# CW340_EdgeConnector.net
KiCad netlist of a schematic drawn in Altium Designer
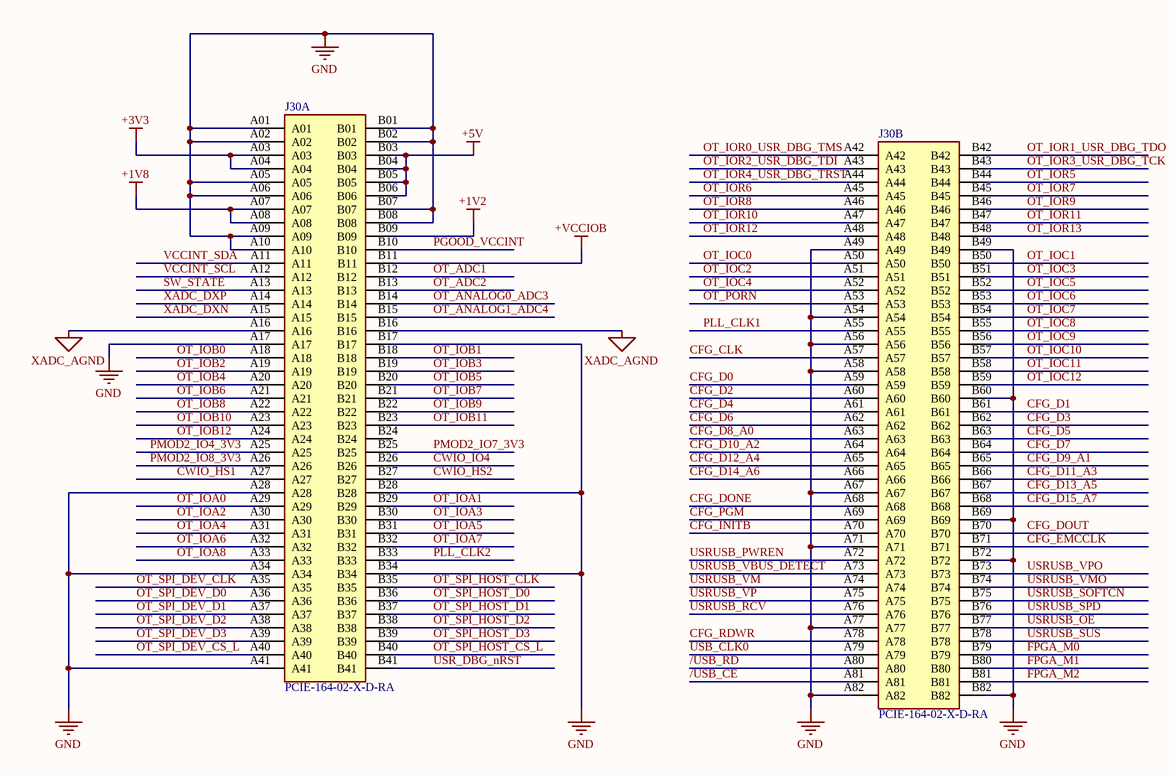
[diagram p0: CW340_EdgeConnector.SchDoc]

(export (version "E")
  (design (tool "Eeschema 10.0.6"))
  (components
    (comp (ref "J30")
      (value "PCIE-164-02-X-D-RA")
      (footprint "SAMTEC_PCIE-164-02-X-D-RA")
      (description "1.00 mm PCI ExpressÂ® Edge Card Connector")
      (fields (field (name "MF") "Samtec"))
      (libsource (lib "PCIE-164-02-X-D-RA") (part "PCIE-164-02-X-D-RA"))
    )
  )
  (nets
    (net (code "1") (name "+1V2") (class "Default")
      (node (ref "J30") (pin "B09") (pinfunction "B09_B09") (pintype "passive"))
    )
    (net (code "2") (name "+1V8") (class "Default")
      (node (ref "J30") (pin "A07") (pinfunction "A07_A07") (pintype "passive"))
      (node (ref "J30") (pin "A08") (pinfunction "A08_A08") (pintype "passive"))
    )
    (net (code "3") (name "+3V3") (class "Default")
      (node (ref "J30") (pin "A03") (pinfunction "A03_A03") (pintype "passive"))
      (node (ref "J30") (pin "A04") (pinfunction "A04_A04") (pintype "passive"))
    )
    (net (code "4") (name "+5V") (class "Default")
      (node (ref "J30") (pin "B03") (pinfunction "B03_B03") (pintype "passive"))
      (node (ref "J30") (pin "B04") (pinfunction "B04_B04") (pintype "passive"))
      (node (ref "J30") (pin "B05") (pinfunction "B05_B05") (pintype "passive"))
      (node (ref "J30") (pin "B06") (pinfunction "B06_B06") (pintype "passive"))
    )
    (net (code "5") (name "+VCCIOB") (class "Default")
      (node (ref "J30") (pin "B11") (pinfunction "B11_B11") (pintype "passive"))
    )
    (net (code "6") (name "/CFG_CLK") (class "Default")
      (node (ref "J30") (pin "A57") (pinfunction "A57_A57") (pintype "passive"))
    )
    (net (code "7") (name "/CFG_D0") (class "Default")
      (node (ref "J30") (pin "A59") (pinfunction "A59_A59") (pintype "passive"))
    )
    (net (code "8") (name "/CFG_D1") (class "Default")
      (node (ref "J30") (pin "B61") (pinfunction "B61_B61") (pintype "passive"))
    )
    (net (code "9") (name "/CFG_D2") (class "Default")
      (node (ref "J30") (pin "A60") (pinfunction "A60_A60") (pintype "passive"))
    )
    (net (code "10") (name "/CFG_D3") (class "Default")
      (node (ref "J30") (pin "B62") (pinfunction "B62_B62") (pintype "passive"))
    )
    (net (code "11") (name "/CFG_D4") (class "Default")
      (node (ref "J30") (pin "A61") (pinfunction "A61_A61") (pintype "passive"))
    )
    (net (code "12") (name "/CFG_D5") (class "Default")
      (node (ref "J30") (pin "B63") (pinfunction "B63_B63") (pintype "passive"))
    )
    (net (code "13") (name "/CFG_D6") (class "Default")
      (node (ref "J30") (pin "A62") (pinfunction "A62_A62") (pintype "passive"))
    )
    (net (code "14") (name "/CFG_D7") (class "Default")
      (node (ref "J30") (pin "B64") (pinfunction "B64_B64") (pintype "passive"))
    )
    (net (code "15") (name "/CFG_D8_A0") (class "Default")
      (node (ref "J30") (pin "A63") (pinfunction "A63_A63") (pintype "passive"))
    )
    (net (code "16") (name "/CFG_D9_A1") (class "Default")
      (node (ref "J30") (pin "B65") (pinfunction "B65_B65") (pintype "passive"))
    )
    (net (code "17") (name "/CFG_D10_A2") (class "Default")
      (node (ref "J30") (pin "A64") (pinfunction "A64_A64") (pintype "passive"))
    )
    (net (code "18") (name "/CFG_D11_A3") (class "Default")
      (node (ref "J30") (pin "B66") (pinfunction "B66_B66") (pintype "passive"))
    )
    (net (code "19") (name "/CFG_D12_A4") (class "Default")
      (node (ref "J30") (pin "A65") (pinfunction "A65_A65") (pintype "passive"))
    )
    (net (code "20") (name "/CFG_D13_A5") (class "Default")
      (node (ref "J30") (pin "B67") (pinfunction "B67_B67") (pintype "passive"))
    )
    (net (code "21") (name "/CFG_D14_A6") (class "Default")
      (node (ref "J30") (pin "A66") (pinfunction "A66_A66") (pintype "passive"))
    )
    (net (code "22") (name "/CFG_D15_A7") (class "Default")
      (node (ref "J30") (pin "B68") (pinfunction "B68_B68") (pintype "passive"))
    )
    (net (code "23") (name "/CFG_DONE") (class "Default")
      (node (ref "J30") (pin "A68") (pinfunction "A68_A68") (pintype "passive"))
    )
    (net (code "24") (name "/CFG_DOUT") (class "Default")
      (node (ref "J30") (pin "B70") (pinfunction "B70_B70") (pintype "passive"))
    )
    (net (code "25") (name "/CFG_EMCCLK") (class "Default")
      (node (ref "J30") (pin "B71") (pinfunction "B71_B71") (pintype "passive"))
    )
    (net (code "26") (name "/CFG_INITB") (class "Default")
      (node (ref "J30") (pin "A70") (pinfunction "A70_A70") (pintype "passive"))
    )
    (net (code "27") (name "/CFG_PGM") (class "Default")
      (node (ref "J30") (pin "A69") (pinfunction "A69_A69") (pintype "passive"))
    )
    (net (code "28") (name "/CFG_RDWR") (class "Default")
      (node (ref "J30") (pin "A78") (pinfunction "A78_A78") (pintype "passive"))
    )
    (net (code "29") (name "/CWIO_HS1") (class "Default")
      (node (ref "J30") (pin "A27") (pinfunction "A27_A27") (pintype "passive"))
    )
    (net (code "30") (name "/CWIO_HS2") (class "Default")
      (node (ref "J30") (pin "B27") (pinfunction "B27_B27") (pintype "passive"))
    )
    (net (code "31") (name "/CWIO_IO4") (class "Default")
      (node (ref "J30") (pin "B26") (pinfunction "B26_B26") (pintype "passive"))
    )
    (net (code "32") (name "/FPGA_M0") (class "Default")
      (node (ref "J30") (pin "B79") (pinfunction "B79_B79") (pintype "passive"))
    )
    (net (code "33") (name "/FPGA_M1") (class "Default")
      (node (ref "J30") (pin "B80") (pinfunction "B80_B80") (pintype "passive"))
    )
    (net (code "34") (name "/FPGA_M2") (class "Default")
      (node (ref "J30") (pin "B81") (pinfunction "B81_B81") (pintype "passive"))
    )
    (net (code "35") (name "/OT_ADC1") (class "Default")
      (node (ref "J30") (pin "B12") (pinfunction "B12_B12") (pintype "passive"))
    )
    (net (code "36") (name "/OT_ADC2") (class "Default")
      (node (ref "J30") (pin "B13") (pinfunction "B13_B13") (pintype "passive"))
    )
    (net (code "37") (name "/OT_ANALOG0_ADC3") (class "Default")
      (node (ref "J30") (pin "B14") (pinfunction "B14_B14") (pintype "passive"))
    )
    (net (code "38") (name "/OT_ANALOG1_ADC4") (class "Default")
      (node (ref "J30") (pin "B15") (pinfunction "B15_B15") (pintype "passive"))
    )
    (net (code "39") (name "/OT_IOA0") (class "Default")
      (node (ref "J30") (pin "A29") (pinfunction "A29_A29") (pintype "passive"))
    )
    (net (code "40") (name "/OT_IOA1") (class "Default")
      (node (ref "J30") (pin "B29") (pinfunction "B29_B29") (pintype "passive"))
    )
    (net (code "41") (name "/OT_IOA2") (class "Default")
      (node (ref "J30") (pin "A30") (pinfunction "A30_A30") (pintype "passive"))
    )
    (net (code "42") (name "/OT_IOA3") (class "Default")
      (node (ref "J30") (pin "B30") (pinfunction "B30_B30") (pintype "passive"))
    )
    (net (code "43") (name "/OT_IOA4") (class "Default")
      (node (ref "J30") (pin "A31") (pinfunction "A31_A31") (pintype "passive"))
    )
    (net (code "44") (name "/OT_IOA5") (class "Default")
      (node (ref "J30") (pin "B31") (pinfunction "B31_B31") (pintype "passive"))
    )
    (net (code "45") (name "/OT_IOA6") (class "Default")
      (node (ref "J30") (pin "A32") (pinfunction "A32_A32") (pintype "passive"))
    )
    (net (code "46") (name "/OT_IOA7") (class "Default")
      (node (ref "J30") (pin "B32") (pinfunction "B32_B32") (pintype "passive"))
    )
    (net (code "47") (name "/OT_IOA8") (class "Default")
      (node (ref "J30") (pin "A33") (pinfunction "A33_A33") (pintype "passive"))
    )
    (net (code "48") (name "/OT_IOB0") (class "Default")
      (node (ref "J30") (pin "A18") (pinfunction "A18_A18") (pintype "passive"))
    )
    (net (code "49") (name "/OT_IOB1") (class "Default")
      (node (ref "J30") (pin "B18") (pinfunction "B18_B18") (pintype "passive"))
    )
    (net (code "50") (name "/OT_IOB2") (class "Default")
      (node (ref "J30") (pin "A19") (pinfunction "A19_A19") (pintype "passive"))
    )
    (net (code "51") (name "/OT_IOB3") (class "Default")
      (node (ref "J30") (pin "B19") (pinfunction "B19_B19") (pintype "passive"))
    )
    (net (code "52") (name "/OT_IOB4") (class "Default")
      (node (ref "J30") (pin "A20") (pinfunction "A20_A20") (pintype "passive"))
    )
    (net (code "53") (name "/OT_IOB5") (class "Default")
      (node (ref "J30") (pin "B20") (pinfunction "B20_B20") (pintype "passive"))
    )
    (net (code "54") (name "/OT_IOB6") (class "Default")
      (node (ref "J30") (pin "A21") (pinfunction "A21_A21") (pintype "passive"))
    )
    (net (code "55") (name "/OT_IOB7") (class "Default")
      (node (ref "J30") (pin "B21") (pinfunction "B21_B21") (pintype "passive"))
    )
    (net (code "56") (name "/OT_IOB8") (class "Default")
      (node (ref "J30") (pin "A22") (pinfunction "A22_A22") (pintype "passive"))
    )
    (net (code "57") (name "/OT_IOB9") (class "Default")
      (node (ref "J30") (pin "B22") (pinfunction "B22_B22") (pintype "passive"))
    )
    (net (code "58") (name "/OT_IOB10") (class "Default")
      (node (ref "J30") (pin "A23") (pinfunction "A23_A23") (pintype "passive"))
    )
    (net (code "59") (name "/OT_IOB11") (class "Default")
      (node (ref "J30") (pin "B23") (pinfunction "B23_B23") (pintype "passive"))
    )
    (net (code "60") (name "/OT_IOB12") (class "Default")
      (node (ref "J30") (pin "A24") (pinfunction "A24_A24") (pintype "passive"))
    )
    (net (code "61") (name "/OT_IOC0") (class "Default")
      (node (ref "J30") (pin "A50") (pinfunction "A50_A50") (pintype "passive"))
    )
    (net (code "62") (name "/OT_IOC1") (class "Default")
      (node (ref "J30") (pin "B50") (pinfunction "B50_B50") (pintype "passive"))
    )
    (net (code "63") (name "/OT_IOC2") (class "Default")
      (node (ref "J30") (pin "A51") (pinfunction "A51_A51") (pintype "passive"))
    )
    (net (code "64") (name "/OT_IOC3") (class "Default")
      (node (ref "J30") (pin "B51") (pinfunction "B51_B51") (pintype "passive"))
    )
    (net (code "65") (name "/OT_IOC4") (class "Default")
      (node (ref "J30") (pin "A52") (pinfunction "A52_A52") (pintype "passive"))
    )
    (net (code "66") (name "/OT_IOC5") (class "Default")
      (node (ref "J30") (pin "B52") (pinfunction "B52_B52") (pintype "passive"))
    )
    (net (code "67") (name "/OT_IOC6") (class "Default")
      (node (ref "J30") (pin "B53") (pinfunction "B53_B53") (pintype "passive"))
    )
    (net (code "68") (name "/OT_IOC7") (class "Default")
      (node (ref "J30") (pin "B54") (pinfunction "B54_B54") (pintype "passive"))
    )
    (net (code "69") (name "/OT_IOC8") (class "Default")
      (node (ref "J30") (pin "B55") (pinfunction "B55_B55") (pintype "passive"))
    )
    (net (code "70") (name "/OT_IOC9") (class "Default")
      (node (ref "J30") (pin "B56") (pinfunction "B56_B56") (pintype "passive"))
    )
    (net (code "71") (name "/OT_IOC10") (class "Default")
      (node (ref "J30") (pin "B57") (pinfunction "B57_B57") (pintype "passive"))
    )
    (net (code "72") (name "/OT_IOC11") (class "Default")
      (node (ref "J30") (pin "B58") (pinfunction "B58_B58") (pintype "passive"))
    )
    (net (code "73") (name "/OT_IOC12") (class "Default")
      (node (ref "J30") (pin "B59") (pinfunction "B59_B59") (pintype "passive"))
    )
    (net (code "74") (name "/OT_IOR0_USR_DBG_TMS") (class "Default")
      (node (ref "J30") (pin "A42") (pinfunction "A42_A42") (pintype "passive"))
    )
    (net (code "75") (name "/OT_IOR1_USR_DBG_TDO") (class "Default")
      (node (ref "J30") (pin "B42") (pinfunction "B42_B42") (pintype "passive"))
    )
    (net (code "76") (name "/OT_IOR2_USR_DBG_TDI") (class "Default")
      (node (ref "J30") (pin "A43") (pinfunction "A43_A43") (pintype "passive"))
    )
    (net (code "77") (name "/OT_IOR3_USR_DBG_TCK") (class "Default")
      (node (ref "J30") (pin "B43") (pinfunction "B43_B43") (pintype "passive"))
    )
    (net (code "78") (name "/OT_IOR4_USR_DBG_TRST") (class "Default")
      (node (ref "J30") (pin "A44") (pinfunction "A44_A44") (pintype "passive"))
    )
    (net (code "79") (name "/OT_IOR5") (class "Default")
      (node (ref "J30") (pin "B44") (pinfunction "B44_B44") (pintype "passive"))
    )
    (net (code "80") (name "/OT_IOR6") (class "Default")
      (node (ref "J30") (pin "A45") (pinfunction "A45_A45") (pintype "passive"))
    )
    (net (code "81") (name "/OT_IOR7") (class "Default")
      (node (ref "J30") (pin "B45") (pinfunction "B45_B45") (pintype "passive"))
    )
    (net (code "82") (name "/OT_IOR8") (class "Default")
      (node (ref "J30") (pin "A46") (pinfunction "A46_A46") (pintype "passive"))
    )
    (net (code "83") (name "/OT_IOR9") (class "Default")
      (node (ref "J30") (pin "B46") (pinfunction "B46_B46") (pintype "passive"))
    )
    (net (code "84") (name "/OT_IOR10") (class "Default")
      (node (ref "J30") (pin "A47") (pinfunction "A47_A47") (pintype "passive"))
    )
    (net (code "85") (name "/OT_IOR11") (class "Default")
      (node (ref "J30") (pin "B47") (pinfunction "B47_B47") (pintype "passive"))
    )
    (net (code "86") (name "/OT_IOR12") (class "Default")
      (node (ref "J30") (pin "A48") (pinfunction "A48_A48") (pintype "passive"))
    )
    (net (code "87") (name "/OT_IOR13") (class "Default")
      (node (ref "J30") (pin "B48") (pinfunction "B48_B48") (pintype "passive"))
    )
    (net (code "88") (name "/OT_PORN") (class "Default")
      (node (ref "J30") (pin "A53") (pinfunction "A53_A53") (pintype "passive"))
    )
    (net (code "89") (name "/OT_SPI_DEV_CLK") (class "Default")
      (node (ref "J30") (pin "A35") (pinfunction "A35_A35") (pintype "passive"))
    )
    (net (code "90") (name "/OT_SPI_DEV_CS_L") (class "Default")
      (node (ref "J30") (pin "A40") (pinfunction "A40_A40") (pintype "passive"))
    )
    (net (code "91") (name "/OT_SPI_DEV_D0") (class "Default")
      (node (ref "J30") (pin "A36") (pinfunction "A36_A36") (pintype "passive"))
    )
    (net (code "92") (name "/OT_SPI_DEV_D1") (class "Default")
      (node (ref "J30") (pin "A37") (pinfunction "A37_A37") (pintype "passive"))
    )
    (net (code "93") (name "/OT_SPI_DEV_D2") (class "Default")
      (node (ref "J30") (pin "A38") (pinfunction "A38_A38") (pintype "passive"))
    )
    (net (code "94") (name "/OT_SPI_DEV_D3") (class "Default")
      (node (ref "J30") (pin "A39") (pinfunction "A39_A39") (pintype "passive"))
    )
    (net (code "95") (name "/OT_SPI_HOST_CLK") (class "Default")
      (node (ref "J30") (pin "B35") (pinfunction "B35_B35") (pintype "passive"))
    )
    (net (code "96") (name "/OT_SPI_HOST_CS_L") (class "Default")
      (node (ref "J30") (pin "B40") (pinfunction "B40_B40") (pintype "passive"))
    )
    (net (code "97") (name "/OT_SPI_HOST_D0") (class "Default")
      (node (ref "J30") (pin "B36") (pinfunction "B36_B36") (pintype "passive"))
    )
    (net (code "98") (name "/OT_SPI_HOST_D1") (class "Default")
      (node (ref "J30") (pin "B37") (pinfunction "B37_B37") (pintype "passive"))
    )
    (net (code "99") (name "/OT_SPI_HOST_D2") (class "Default")
      (node (ref "J30") (pin "B38") (pinfunction "B38_B38") (pintype "passive"))
    )
    (net (code "100") (name "/OT_SPI_HOST_D3") (class "Default")
      (node (ref "J30") (pin "B39") (pinfunction "B39_B39") (pintype "passive"))
    )
    (net (code "101") (name "/PGOOD_VCCINT") (class "Default")
      (node (ref "J30") (pin "B10") (pinfunction "B10_B10") (pintype "passive"))
    )
    (net (code "102") (name "/PLL_CLK1") (class "Default")
      (node (ref "J30") (pin "A55") (pinfunction "A55_A55") (pintype "passive"))
    )
    (net (code "103") (name "/PLL_CLK2") (class "Default")
      (node (ref "J30") (pin "B33") (pinfunction "B33_B33") (pintype "passive"))
    )
    (net (code "104") (name "/PMOD2_IO4_3V3") (class "Default")
      (node (ref "J30") (pin "A25") (pinfunction "A25_A25") (pintype "passive"))
    )
    (net (code "105") (name "/PMOD2_IO7_3V3") (class "Default")
      (node (ref "J30") (pin "B25") (pinfunction "B25_B25") (pintype "passive"))
    )
    (net (code "106") (name "/PMOD2_IO8_3V3") (class "Default")
      (node (ref "J30") (pin "A26") (pinfunction "A26_A26") (pintype "passive"))
    )
    (net (code "107") (name "/SW_STATE") (class "Default")
      (node (ref "J30") (pin "A13") (pinfunction "A13_A13") (pintype "passive"))
    )
    (net (code "108") (name "/USB_CLK0") (class "Default")
      (node (ref "J30") (pin "A79") (pinfunction "A79_A79") (pintype "passive"))
    )
    (net (code "109") (name "/USRUSB_OE") (class "Default")
      (node (ref "J30") (pin "B77") (pinfunction "B77_B77") (pintype "passive"))
    )
    (net (code "110") (name "/USRUSB_PWREN") (class "Default")
      (node (ref "J30") (pin "A72") (pinfunction "A72_A72") (pintype "passive"))
    )
    (net (code "111") (name "/USRUSB_RCV") (class "Default")
      (node (ref "J30") (pin "A76") (pinfunction "A76_A76") (pintype "passive"))
    )
    (net (code "112") (name "/USRUSB_SOFTCN") (class "Default")
      (node (ref "J30") (pin "B75") (pinfunction "B75_B75") (pintype "passive"))
    )
    (net (code "113") (name "/USRUSB_SPD") (class "Default")
      (node (ref "J30") (pin "B76") (pinfunction "B76_B76") (pintype "passive"))
    )
    (net (code "114") (name "/USRUSB_SUS") (class "Default")
      (node (ref "J30") (pin "B78") (pinfunction "B78_B78") (pintype "passive"))
    )
    (net (code "115") (name "/USRUSB_VBUS_DETECT") (class "Default")
      (node (ref "J30") (pin "A73") (pinfunction "A73_A73") (pintype "passive"))
    )
    (net (code "116") (name "/USRUSB_VM") (class "Default")
      (node (ref "J30") (pin "A74") (pinfunction "A74_A74") (pintype "passive"))
    )
    (net (code "117") (name "/USRUSB_VMO") (class "Default")
      (node (ref "J30") (pin "B74") (pinfunction "B74_B74") (pintype "passive"))
    )
    (net (code "118") (name "/USRUSB_VP") (class "Default")
      (node (ref "J30") (pin "A75") (pinfunction "A75_A75") (pintype "passive"))
    )
    (net (code "119") (name "/USRUSB_VPO") (class "Default")
      (node (ref "J30") (pin "B73") (pinfunction "B73_B73") (pintype "passive"))
    )
    (net (code "120") (name "/USR_DBG_nRST") (class "Default")
      (node (ref "J30") (pin "B41") (pinfunction "B41_B41") (pintype "passive"))
    )
    (net (code "121") (name "/VCCINT_SCL") (class "Default")
      (node (ref "J30") (pin "A12") (pinfunction "A12_A12") (pintype "passive"))
    )
    (net (code "122") (name "/VCCINT_SDA") (class "Default")
      (node (ref "J30") (pin "A11") (pinfunction "A11_A11") (pintype "passive"))
    )
    (net (code "123") (name "/XADC_DXN") (class "Default")
      (node (ref "J30") (pin "A15") (pinfunction "A15_A15") (pintype "passive"))
    )
    (net (code "124") (name "/XADC_DXP") (class "Default")
      (node (ref "J30") (pin "A14") (pinfunction "A14_A14") (pintype "passive"))
    )
    (net (code "125") (name "/{slash}USB_CE") (class "Default")
      (node (ref "J30") (pin "A81") (pinfunction "A81_A81") (pintype "passive"))
    )
    (net (code "126") (name "/{slash}USB_RD") (class "Default")
      (node (ref "J30") (pin "A80") (pinfunction "A80_A80") (pintype "passive"))
    )
    (net (code "127") (name "GND") (class "Default")
      (node (ref "J30") (pin "A01") (pinfunction "A01_A01") (pintype "passive"))
      (node (ref "J30") (pin "A02") (pinfunction "A02_A02") (pintype "passive"))
      (node (ref "J30") (pin "A05") (pinfunction "A05_A05") (pintype "passive"))
      (node (ref "J30") (pin "A06") (pinfunction "A06_A06") (pintype "passive"))
      (node (ref "J30") (pin "A09") (pinfunction "A09_A09") (pintype "passive"))
      (node (ref "J30") (pin "A10") (pinfunction "A10_A10") (pintype "passive"))
      (node (ref "J30") (pin "A17") (pinfunction "A17_A17") (pintype "passive"))
      (node (ref "J30") (pin "A28") (pinfunction "A28_A28") (pintype "passive"))
      (node (ref "J30") (pin "A34") (pinfunction "A34_A34") (pintype "passive"))
      (node (ref "J30") (pin "A41") (pinfunction "A41_A41") (pintype "passive"))
      (node (ref "J30") (pin "A49") (pinfunction "A49_A49") (pintype "passive"))
      (node (ref "J30") (pin "A54") (pinfunction "A54_A54") (pintype "passive"))
      (node (ref "J30") (pin "A56") (pinfunction "A56_A56") (pintype "passive"))
      (node (ref "J30") (pin "A58") (pinfunction "A58_A58") (pintype "passive"))
      (node (ref "J30") (pin "A67") (pinfunction "A67_A67") (pintype "passive"))
      (node (ref "J30") (pin "A71") (pinfunction "A71_A71") (pintype "passive"))
      (node (ref "J30") (pin "A77") (pinfunction "A77_A77") (pintype "passive"))
      (node (ref "J30") (pin "A82") (pinfunction "A82_A82") (pintype "passive"))
      (node (ref "J30") (pin "B01") (pinfunction "B01_B01") (pintype "passive"))
      (node (ref "J30") (pin "B02") (pinfunction "B02_B02") (pintype "passive"))
      (node (ref "J30") (pin "B07") (pinfunction "B07_B07") (pintype "passive"))
      (node (ref "J30") (pin "B08") (pinfunction "B08_B08") (pintype "passive"))
      (node (ref "J30") (pin "B17") (pinfunction "B17_B17") (pintype "passive"))
      (node (ref "J30") (pin "B28") (pinfunction "B28_B28") (pintype "passive"))
      (node (ref "J30") (pin "B34") (pinfunction "B34_B34") (pintype "passive"))
      (node (ref "J30") (pin "B49") (pinfunction "B49_B49") (pintype "passive"))
      (node (ref "J30") (pin "B60") (pinfunction "B60_B60") (pintype "passive"))
      (node (ref "J30") (pin "B69") (pinfunction "B69_B69") (pintype "passive"))
      (node (ref "J30") (pin "B72") (pinfunction "B72_B72") (pintype "passive"))
      (node (ref "J30") (pin "B82") (pinfunction "B82_B82") (pintype "passive"))
    )
    (net (code "128") (name "XADC_AGND") (class "Default")
      (node (ref "J30") (pin "A16") (pinfunction "A16_A16") (pintype "passive"))
      (node (ref "J30") (pin "B16") (pinfunction "B16_B16") (pintype "passive"))
    )
    (net (code "129") (name "unconnected-(J30-PadB24)") (class "Default")
      (node (ref "J30") (pin "B24") (pinfunction "B24_B24") (pintype "passive"))
    )
  )
)
